# Example_for_libraries_reference.net
KiCad netlist of a schematic drawn in EAGLE
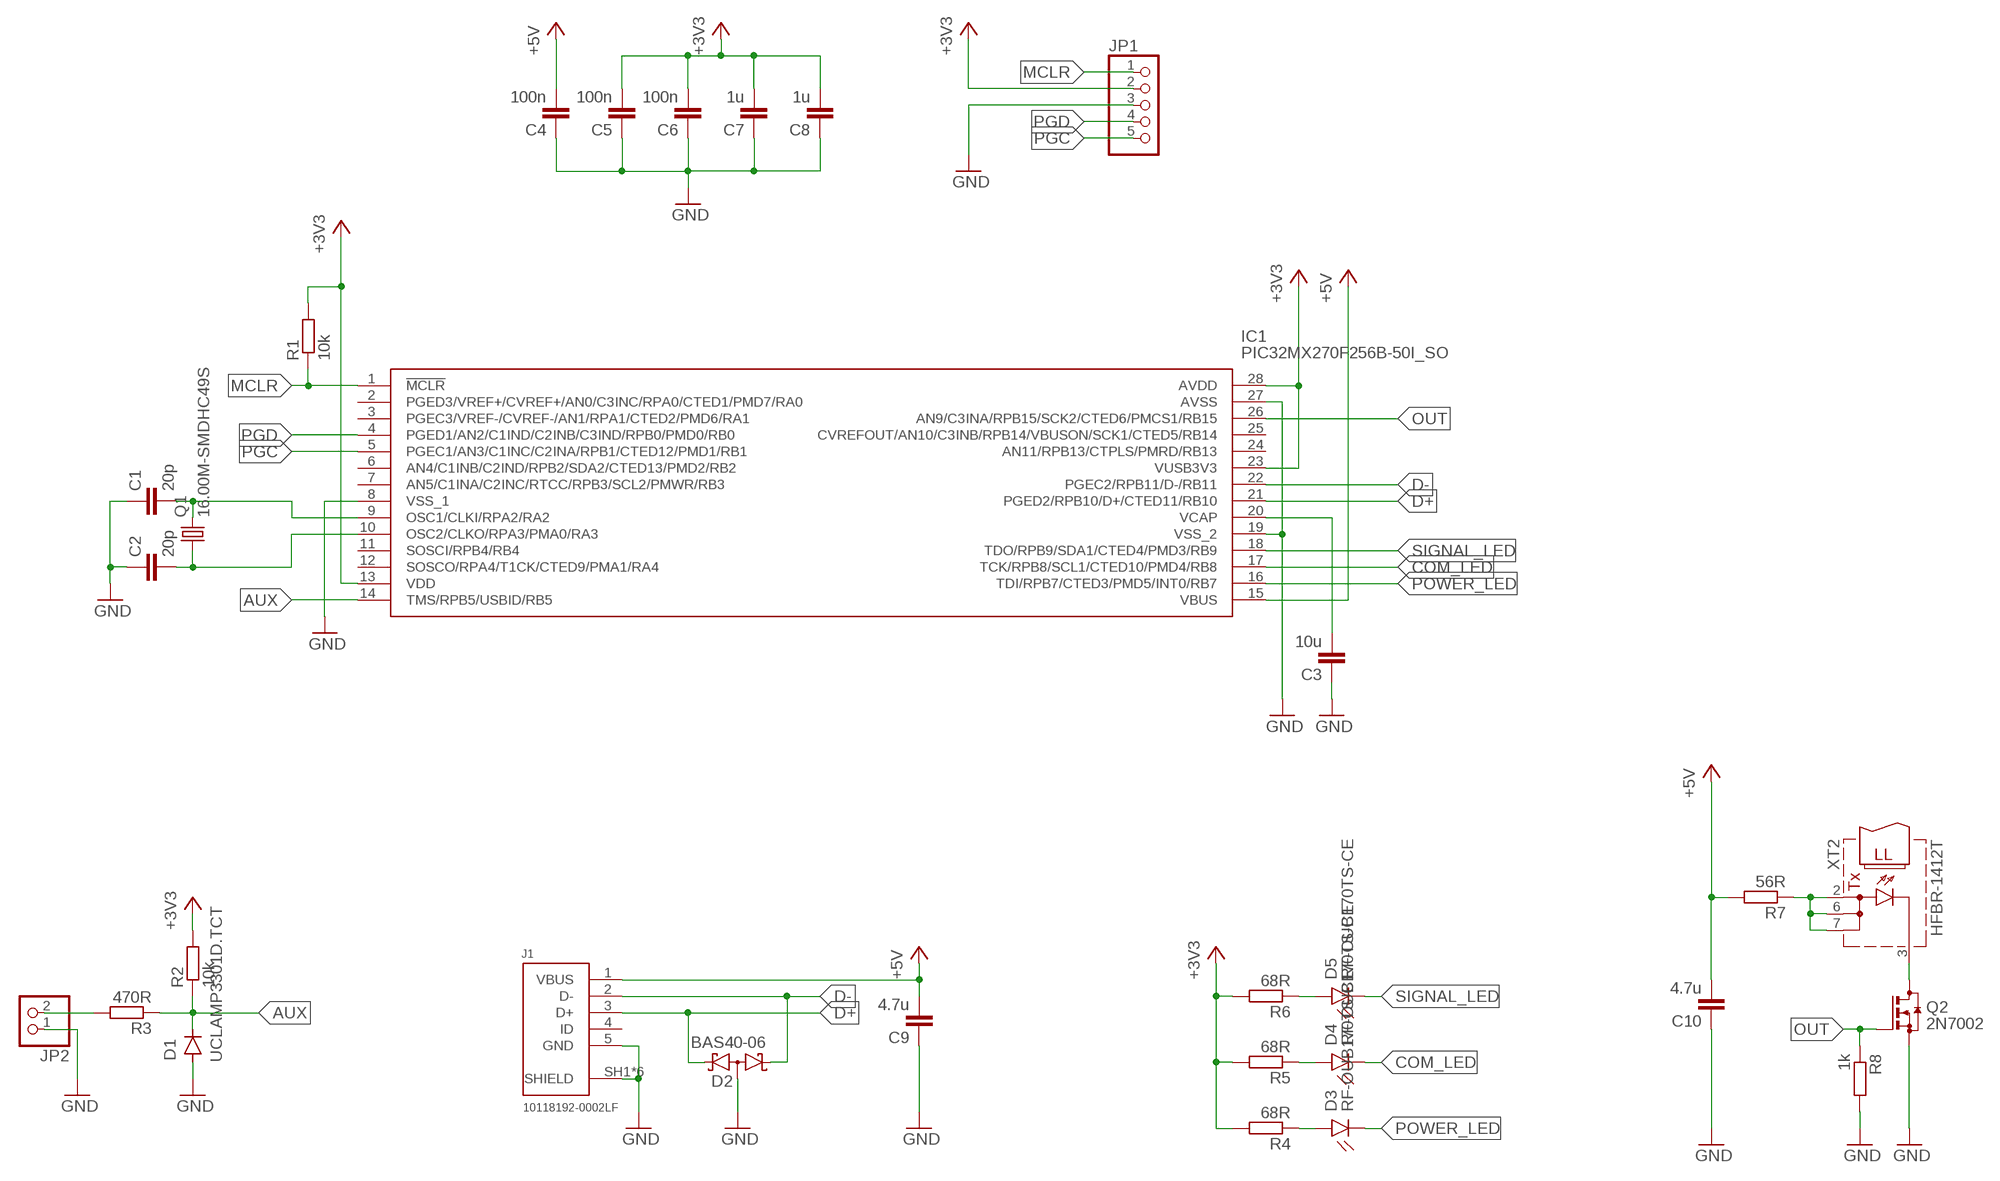
[diagram p0: schematic, sheet 1]

(export (version "E")
  (design (tool "Eeschema 10.0.6"))
  (components
    (comp (ref "C1")
      (value "20p")
      (footprint "eagle-import:C0805")
      (libsource (lib "eagle-import") (part "C-EUC0805"))
    )
    (comp (ref "C2")
      (value "20p")
      (footprint "eagle-import:C0805")
      (libsource (lib "eagle-import") (part "C-EUC0805"))
    )
    (comp (ref "C3")
      (value "10u")
      (footprint "eagle-import:C0805")
      (libsource (lib "eagle-import") (part "C-EUC0805"))
    )
    (comp (ref "C4")
      (value "100n")
      (footprint "eagle-import:C0805")
      (libsource (lib "eagle-import") (part "C-EUC0805"))
    )
    (comp (ref "C5")
      (value "100n")
      (footprint "eagle-import:C0805")
      (libsource (lib "eagle-import") (part "C-EUC0805"))
    )
    (comp (ref "C6")
      (value "100n")
      (footprint "eagle-import:C0805")
      (libsource (lib "eagle-import") (part "C-EUC0805"))
    )
    (comp (ref "C7")
      (value "1u")
      (footprint "eagle-import:C0805")
      (libsource (lib "eagle-import") (part "C-EUC0805"))
    )
    (comp (ref "C8")
      (value "1u")
      (footprint "eagle-import:C0805")
      (libsource (lib "eagle-import") (part "C-EUC0805"))
    )
    (comp (ref "C9")
      (value "4.7u")
      (footprint "eagle-import:C0805")
      (libsource (lib "eagle-import") (part "C-EUC0805"))
    )
    (comp (ref "C10")
      (value "4.7u")
      (footprint "eagle-import:C0805")
      (libsource (lib "eagle-import") (part "C-EUC0805"))
    )
    (comp (ref "D1")
      (value "UCLAMP3301D.TCT")
      (footprint "eagle-import:SOD-323")
      (fields
        (field (name "DIGIKEY_PART_NUMBER") "1N4148WSFSTR-ND")
        (field (name "MANUFACTURER") "Diodes Incorporated")
        (field (name "MPN") "1N4148WS")
        (field (name "CREATED_BY") "PCBLayout.com")
      )
      (libsource (lib "eagle-import") (part "1N4148WS"))
    )
    (comp (ref "D2")
      (value "BAS40-06")
      (footprint "eagle-import:SOT23")
      (libsource (lib "eagle-import") (part "BAS40-06"))
    )
    (comp (ref "D3")
      (value "RF-OUB170TS-CE")
      (footprint "eagle-import:LEDC2012X110N_FLAT-B")
      (libsource (lib "eagle-import") (part "CHIP-FLAT-B_0805"))
    )
    (comp (ref "D4")
      (value "RF-OUB170TS-CE")
      (footprint "eagle-import:LEDC2012X110N_FLAT-B")
      (libsource (lib "eagle-import") (part "CHIP-FLAT-B_0805"))
    )
    (comp (ref "D5")
      (value "RF-OUB170TS-CE")
      (footprint "eagle-import:LEDC2012X110N_FLAT-B")
      (libsource (lib "eagle-import") (part "CHIP-FLAT-B_0805"))
    )
    (comp (ref "IC1")
      (value "PIC32MX270F256B-50I_SO")
      (footprint "eagle-import:SOIC127P1030X265-28N")
      (fields
        (field (name "MANUFACTURER_PART_NUMBER") "PIC32MX270F256B-50I/SO")
        (field (name "MOUSER_PART_NUMBER") "579-32MX270F256B5ISO")
      )
      (libsource (lib "eagle-import") (part "PIC32MX270F256B-50I_SO"))
    )
    (comp (ref "J1")
      (value "10118192-0002LF")
      (footprint "eagle-import:10118192-0002LF")
      (fields
        (field (name "DIGIKEY_PARTNO") "609-5379-2-ND")
        (field (name "MANUFACTURER") "Amphenol ICC (FCI)")
        (field (name "CREATED_BY") "PCBLayout.com")
      )
      (libsource (lib "eagle-import") (part "10118192-0002LF"))
    )
    (comp (ref "JP1")
      (value "PINHD-1X5")
      (footprint "eagle-import:1X05")
      (libsource (lib "eagle-import") (part "PINHD-1X5"))
    )
    (comp (ref "JP2")
      (value "PINHD-1X2")
      (footprint "eagle-import:1X02")
      (libsource (lib "eagle-import") (part "PINHD-1X2"))
    )
    (comp (ref "Q1")
      (value "16.00M-SMDHC49S")
      (footprint "eagle-import:SM49")
      (libsource (lib "eagle-import") (part "CRYSTALSM49"))
    )
    (comp (ref "Q2")
      (value "2N7002")
      (footprint "eagle-import:SOT23")
      (libsource (lib "eagle-import") (part "BSS123"))
    )
    (comp (ref "R1")
      (value "10k")
      (footprint "eagle-import:R0805")
      (libsource (lib "eagle-import") (part "R-EU_R0805"))
    )
    (comp (ref "R2")
      (value "10k")
      (footprint "eagle-import:R0805")
      (libsource (lib "eagle-import") (part "R-EU_R0805"))
    )
    (comp (ref "R3")
      (value "470R")
      (footprint "eagle-import:R0805")
      (libsource (lib "eagle-import") (part "R-EU_R0805"))
    )
    (comp (ref "R4")
      (value "68R")
      (footprint "eagle-import:R0805")
      (libsource (lib "eagle-import") (part "R-EU_R0805"))
    )
    (comp (ref "R5")
      (value "68R")
      (footprint "eagle-import:R0805")
      (libsource (lib "eagle-import") (part "R-EU_R0805"))
    )
    (comp (ref "R6")
      (value "68R")
      (footprint "eagle-import:R0805")
      (libsource (lib "eagle-import") (part "R-EU_R0805"))
    )
    (comp (ref "R7")
      (value "56R")
      (footprint "eagle-import:R0805")
      (libsource (lib "eagle-import") (part "R-EU_R0805"))
    )
    (comp (ref "R8")
      (value "1k")
      (footprint "eagle-import:R0805")
      (libsource (lib "eagle-import") (part "R-EU_R0805"))
    )
    (comp (ref "XT2")
      (value "HFBR-1412T")
      (footprint "eagle-import:HFBR-X41XT")
      (fields (field (name "MF") "AGILENT TECHNOLOGIES"))
      (libsource (lib "eagle-import") (part "HFBR-1412T"))
    )
  )
  (nets
    (net (code "1") (name "+3V3") (class "Default")
      (node (ref "C5") (pin "2") (pinfunction "2_2") (pintype "passive"))
      (node (ref "C6") (pin "2") (pinfunction "2_2") (pintype "passive"))
      (node (ref "C7") (pin "2") (pinfunction "2_2") (pintype "passive"))
      (node (ref "C8") (pin "2") (pinfunction "2_2") (pintype "passive"))
      (node (ref "IC1") (pin "13") (pinfunction "VDD_13") (pintype "bidirectional"))
      (node (ref "IC1") (pin "23") (pinfunction "VUSB3V3_23") (pintype "bidirectional"))
      (node (ref "IC1") (pin "28") (pinfunction "AVDD_28") (pintype "bidirectional"))
      (node (ref "JP1") (pin "2") (pinfunction "2_2") (pintype "passive"))
      (node (ref "R1") (pin "2") (pinfunction "2_2") (pintype "passive"))
      (node (ref "R2") (pin "2") (pinfunction "2_2") (pintype "passive"))
      (node (ref "R4") (pin "2") (pinfunction "2_2") (pintype "passive"))
      (node (ref "R5") (pin "2") (pinfunction "2_2") (pintype "passive"))
      (node (ref "R6") (pin "2") (pinfunction "2_2") (pintype "passive"))
    )
    (net (code "2") (name "+5V") (class "Default")
      (node (ref "C10") (pin "2") (pinfunction "2_2") (pintype "passive"))
      (node (ref "C4") (pin "2") (pinfunction "2_2") (pintype "passive"))
      (node (ref "C9") (pin "2") (pinfunction "2_2") (pintype "passive"))
      (node (ref "IC1") (pin "15") (pinfunction "VBUS_15") (pintype "bidirectional"))
      (node (ref "J1") (pin "1") (pinfunction "VBUS_1") (pintype "passive"))
      (node (ref "R7") (pin "2") (pinfunction "2_2") (pintype "passive"))
    )
    (net (code "3") (name "AUX") (class "Default")
      (node (ref "D1") (pin "C") (pinfunction "C_C") (pintype "passive"))
      (node (ref "IC1") (pin "14") (pinfunction "TMS/RPB5/USBID/RB5_14") (pintype "bidirectional"))
      (node (ref "R2") (pin "1") (pinfunction "1_1") (pintype "passive"))
      (node (ref "R3") (pin "1") (pinfunction "1_1") (pintype "passive"))
    )
    (net (code "4") (name "COM_LED") (class "Default")
      (node (ref "D4") (pin "C") (pinfunction "C_C") (pintype "passive"))
      (node (ref "IC1") (pin "17") (pinfunction "TCK/RPB8/SCL1/CTED10/PMD4/RB8_17") (pintype "bidirectional"))
    )
    (net (code "5") (name "D+") (class "Default")
      (node (ref "D2") (pin "2") (pinfunction "K2_2") (pintype "passive"))
      (node (ref "IC1") (pin "21") (pinfunction "PGED2/RPB10/D+/CTED11/RB10_21") (pintype "bidirectional"))
      (node (ref "J1") (pin "3") (pinfunction "D+_3") (pintype "passive"))
    )
    (net (code "6") (name "D-") (class "Default")
      (node (ref "D2") (pin "1") (pinfunction "K1_1") (pintype "passive"))
      (node (ref "IC1") (pin "22") (pinfunction "PGEC2/RPB11/D-/RB11_22") (pintype "bidirectional"))
      (node (ref "J1") (pin "2") (pinfunction "D-_2") (pintype "passive"))
    )
    (net (code "7") (name "GND") (class "Default")
      (node (ref "C1") (pin "1") (pinfunction "1_1") (pintype "passive"))
      (node (ref "C10") (pin "1") (pinfunction "1_1") (pintype "passive"))
      (node (ref "C2") (pin "1") (pinfunction "1_1") (pintype "passive"))
      (node (ref "C3") (pin "1") (pinfunction "1_1") (pintype "passive"))
      (node (ref "C4") (pin "1") (pinfunction "1_1") (pintype "passive"))
      (node (ref "C5") (pin "1") (pinfunction "1_1") (pintype "passive"))
      (node (ref "C6") (pin "1") (pinfunction "1_1") (pintype "passive"))
      (node (ref "C7") (pin "1") (pinfunction "1_1") (pintype "passive"))
      (node (ref "C8") (pin "1") (pinfunction "1_1") (pintype "passive"))
      (node (ref "C9") (pin "1") (pinfunction "1_1") (pintype "passive"))
      (node (ref "D1") (pin "A") (pinfunction "A_A") (pintype "passive"))
      (node (ref "D2") (pin "3") (pinfunction "AA_3") (pintype "passive"))
      (node (ref "IC1") (pin "19") (pinfunction "VSS_2_19") (pintype "bidirectional"))
      (node (ref "IC1") (pin "27") (pinfunction "AVSS_27") (pintype "bidirectional"))
      (node (ref "IC1") (pin "8") (pinfunction "VSS_1_8") (pintype "bidirectional"))
      (node (ref "J1") (pin "5") (pinfunction "GND_5") (pintype "passive"))
      (node (ref "J1") (pin "SH1") (pinfunction "SHIELD_SH1") (pintype "power_in"))
      (node (ref "J1") (pin "SH2") (pinfunction "SHIELD_SH2") (pintype "power_in"))
      (node (ref "J1") (pin "SH3") (pinfunction "SHIELD_SH3") (pintype "power_in"))
      (node (ref "J1") (pin "SH4") (pinfunction "SHIELD_SH4") (pintype "power_in"))
      (node (ref "J1") (pin "SH5") (pinfunction "SHIELD_SH5") (pintype "power_in"))
      (node (ref "J1") (pin "SH6") (pinfunction "SHIELD_SH6") (pintype "power_in"))
      (node (ref "JP1") (pin "3") (pinfunction "3_3") (pintype "passive"))
      (node (ref "JP2") (pin "1") (pinfunction "1_1") (pintype "passive"))
      (node (ref "Q2") (pin "2") (pinfunction "S_2") (pintype "passive"))
      (node (ref "R8") (pin "2") (pinfunction "2_2") (pintype "passive"))
    )
    (net (code "8") (name "MCLR") (class "Default")
      (node (ref "IC1") (pin "1") (pinfunction "~{MCLR}_1") (pintype "bidirectional"))
      (node (ref "JP1") (pin "1") (pinfunction "1_1") (pintype "passive"))
      (node (ref "R1") (pin "1") (pinfunction "1_1") (pintype "passive"))
    )
    (net (code "9") (name "Net-(D3-PadA)") (class "Default")
      (node (ref "D3") (pin "A") (pinfunction "A_A") (pintype "passive"))
      (node (ref "R4") (pin "1") (pinfunction "1_1") (pintype "passive"))
    )
    (net (code "10") (name "Net-(D4-PadA)") (class "Default")
      (node (ref "D4") (pin "A") (pinfunction "A_A") (pintype "passive"))
      (node (ref "R5") (pin "1") (pinfunction "1_1") (pintype "passive"))
    )
    (net (code "11") (name "Net-(D5-PadA)") (class "Default")
      (node (ref "D5") (pin "A") (pinfunction "A_A") (pintype "passive"))
      (node (ref "R6") (pin "1") (pinfunction "1_1") (pintype "passive"))
    )
    (net (code "12") (name "Net-(IC1-OSC1{slash}CLKI{slash}RPA2{slash}RA2)") (class "Default")
      (node (ref "C1") (pin "2") (pinfunction "2_2") (pintype "passive"))
      (node (ref "IC1") (pin "9") (pinfunction "OSC1/CLKI/RPA2/RA2_9") (pintype "bidirectional"))
      (node (ref "Q1") (pin "2") (pinfunction "2_2") (pintype "passive"))
    )
    (net (code "13") (name "Net-(IC1-OSC2{slash}CLKO{slash}RPA3{slash}PMA0{slash}RA3)") (class "Default")
      (node (ref "C2") (pin "2") (pinfunction "2_2") (pintype "passive"))
      (node (ref "IC1") (pin "10") (pinfunction "OSC2/CLKO/RPA3/PMA0/RA3_10") (pintype "bidirectional"))
      (node (ref "Q1") (pin "1") (pinfunction "1_1") (pintype "passive"))
    )
    (net (code "14") (name "Net-(IC1-VCAP)") (class "Default")
      (node (ref "C3") (pin "2") (pinfunction "2_2") (pintype "passive"))
      (node (ref "IC1") (pin "20") (pinfunction "VCAP_20") (pintype "bidirectional"))
    )
    (net (code "15") (name "Net-(JP2-Pad2)") (class "Default")
      (node (ref "JP2") (pin "2") (pinfunction "2_2") (pintype "passive"))
      (node (ref "R3") (pin "2") (pinfunction "2_2") (pintype "passive"))
    )
    (net (code "16") (name "Net-(Q2-D)") (class "Default")
      (node (ref "Q2") (pin "3") (pinfunction "D_3") (pintype "passive"))
      (node (ref "XT2") (pin "3") (pinfunction "C_3") (pintype "passive"))
    )
    (net (code "17") (name "Net-(XT2-A)") (class "Default")
      (node (ref "R7") (pin "1") (pinfunction "1_1") (pintype "passive"))
      (node (ref "XT2") (pin "2") (pinfunction "A_2") (pintype "passive"))
      (node (ref "XT2") (pin "6") (pinfunction "A1_6") (pintype "passive"))
      (node (ref "XT2") (pin "7") (pinfunction "A2_7") (pintype "passive"))
    )
    (net (code "18") (name "OUT") (class "Default")
      (node (ref "IC1") (pin "26") (pinfunction "AN9/C3INA/RPB15/SCK2/CTED6/PMCS1/RB15_26") (pintype "bidirectional"))
      (node (ref "Q2") (pin "1") (pinfunction "G_1") (pintype "passive"))
      (node (ref "R8") (pin "1") (pinfunction "1_1") (pintype "passive"))
    )
    (net (code "19") (name "PGC") (class "Default")
      (node (ref "IC1") (pin "5") (pinfunction "PGEC1/AN3/C1INC/C2INA/RPB1/CTED12/PMD1/RB1_5") (pintype "bidirectional"))
      (node (ref "JP1") (pin "5") (pinfunction "5_5") (pintype "passive"))
    )
    (net (code "20") (name "PGD") (class "Default")
      (node (ref "IC1") (pin "4") (pinfunction "PGED1/AN2/C1IND/C2INB/C3IND/RPB0/PMD0/RB0_4") (pintype "bidirectional"))
      (node (ref "JP1") (pin "4") (pinfunction "4_4") (pintype "passive"))
    )
    (net (code "21") (name "POWER_LED") (class "Default")
      (node (ref "D3") (pin "C") (pinfunction "C_C") (pintype "passive"))
      (node (ref "IC1") (pin "16") (pinfunction "TDI/RPB7/CTED3/PMD5/INT0/RB7_16") (pintype "bidirectional"))
    )
    (net (code "22") (name "SIGNAL_LED") (class "Default")
      (node (ref "D5") (pin "C") (pinfunction "C_C") (pintype "passive"))
      (node (ref "IC1") (pin "18") (pinfunction "TDO/RPB9/SDA1/CTED4/PMD3/RB9_18") (pintype "bidirectional"))
    )
    (net (code "23") (name "unconnected-(IC1-AN4{slash}C1INB{slash}C2IND{slash}RPB2{slash}SDA2{slash}CTED13{slash}PMD2{slash}RB2-Pad6)") (class "Default")
      (node (ref "IC1") (pin "6") (pinfunction "AN4/C1INB/C2IND/RPB2/SDA2/CTED13/PMD2/RB2_6") (pintype "bidirectional"))
    )
    (net (code "24") (name "unconnected-(IC1-AN5{slash}C1INA{slash}C2INC{slash}RTCC{slash}RPB3{slash}SCL2{slash}PMWR{slash}RB3-Pad7)") (class "Default")
      (node (ref "IC1") (pin "7") (pinfunction "AN5/C1INA/C2INC/RTCC/RPB3/SCL2/PMWR/RB3_7") (pintype "bidirectional"))
    )
    (net (code "25") (name "unconnected-(IC1-AN11{slash}RPB13{slash}CTPLS{slash}PMRD{slash}RB13-Pad24)") (class "Default")
      (node (ref "IC1") (pin "24") (pinfunction "AN11/RPB13/CTPLS/PMRD/RB13_24") (pintype "bidirectional"))
    )
    (net (code "26") (name "unconnected-(IC1-CVREFOUT{slash}AN10{slash}C3INB{slash}RPB14{slash}VBUSON{slash}SCK1{slash}CTED5{slash}RB14-Pad25)") (class "Default")
      (node (ref "IC1") (pin "25") (pinfunction "CVREFOUT/AN10/C3INB/RPB14/VBUSON/SCK1/CTED5/RB14_25") (pintype "bidirectional"))
    )
    (net (code "27") (name "unconnected-(IC1-PGEC3{slash}VREF-{slash}CVREF-{slash}AN1{slash}RPA1{slash}CTED2{slash}PMD6{slash}RA1-Pad3)") (class "Default")
      (node (ref "IC1") (pin "3") (pinfunction "PGEC3/VREF-/CVREF-/AN1/RPA1/CTED2/PMD6/RA1_3") (pintype "bidirectional"))
    )
    (net (code "28") (name "unconnected-(IC1-PGED3{slash}VREF+{slash}CVREF+{slash}AN0{slash}C3INC{slash}RPA0{slash}CTED1{slash}PMD7{slash}RA0-Pad2)") (class "Default")
      (node (ref "IC1") (pin "2") (pinfunction "PGED3/VREF+/CVREF+/AN0/C3INC/RPA0/CTED1/PMD7/RA0_2") (pintype "bidirectional"))
    )
    (net (code "29") (name "unconnected-(IC1-SOSCI{slash}RPB4{slash}RB4-Pad11)") (class "Default")
      (node (ref "IC1") (pin "11") (pinfunction "SOSCI/RPB4/RB4_11") (pintype "bidirectional"))
    )
    (net (code "30") (name "unconnected-(IC1-SOSCO{slash}RPA4{slash}T1CK{slash}CTED9{slash}PMA1{slash}RA4-Pad12)") (class "Default")
      (node (ref "IC1") (pin "12") (pinfunction "SOSCO/RPA4/T1CK/CTED9/PMA1/RA4_12") (pintype "bidirectional"))
    )
    (net (code "31") (name "unconnected-(J1-ID-Pad4)") (class "Default")
      (node (ref "J1") (pin "4") (pinfunction "ID_4") (pintype "passive"))
    )
  )
)
